# Solar_Phone_Charger.net
KiCad netlist of a schematic drawn in Altium Designer
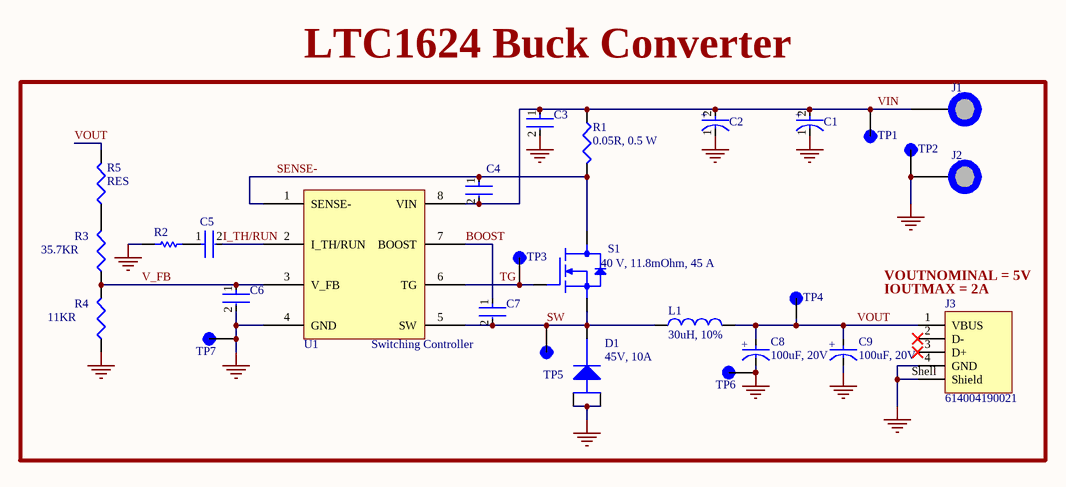
[diagram p0: Solar_Phone_Charger.SchDoc]

(export (version "E")
  (design (tool "Eeschema 10.0.6"))
  (components
    (comp (ref "C1")
      (value "T495X336M035ATE100")
      (footprint "FP-T495X336M035ATE100-MFG")
      (description "CAP TANT 33UF 20% 35V 2917")
      (fields (field (name "TOLERANCE") "20%"))
      (libsource (lib "") (part "203bc49f2ac43e59fd269a8c329ed05_1"))
    )
    (comp (ref "C2")
      (value "T495X336M035ATE100")
      (footprint "FP-T495X336M035ATE100-MFG")
      (description "CAP TANT 33UF 20% 35V 2917")
      (fields (field (name "TOLERANCE") "20%"))
      (libsource (lib "") (part "203bc49f2ac43e59fd269a8c329ed05_1"))
    )
    (comp (ref "C3")
      (value "C1206C104J5RACTU")
      (footprint "FP-C1206C-EB-MFG")
      (fields
        (field (name "MANUFACTURER") "KEMET")
        (field (name "OCTOPART") "https://octopart.com/c1206c104j5ractu-kemet-110335")
        (field (name "TOLERANCE") "0.05")
      )
      (libsource (lib "Altium Content Vault") (part "b4654b650e69147ec39a6b967a45e02"))
    )
    (comp (ref "C4")
      (value "C1206C102F1GACTU")
      (footprint "FP-C1206C-EB-MFG")
      (description "CAP CER 1000PF 100V 1% NP0 1206")
      (fields (field (name "TOLERANCE") "0.01") (field (name "MANUFACTURER") "KEMET"))
      (libsource (lib "Altium Content Vault") (part "b4654b650e69147ec39a6b967a45e02"))
    )
    (comp (ref "C5")
      (value "C0805C471J5GAC7210")
      (footprint "FP-C0805C-DN-MFG")
      (description "C0805 470 pF C0G 30ppm/°C 5.00% 50 V")
      (fields (field (name "TOLERANCE") "0.05") (field (name "MANUFACTURER") "KEMET"))
      (libsource (lib "Altium Content Vault") (part "b4654b650e69147ec39a6b967a45e02"))
    )
    (comp (ref "C6")
      (value "C0805C101K5GAC7210")
      (footprint "FP-C0805C-DN-MFG")
      (description "C0805 100 pF C0G 30ppm/°C 10.00% 50 V")
      (fields
        (field (name "OCTOPART") "https://octopart.com/c0805c101k5gac7210-kemet-11759675")
        (field (name "TOLERANCE") "0.1")
      )
      (libsource (lib "Altium Content Vault") (part "b4654b650e69147ec39a6b967a45e02"))
    )
    (comp (ref "C7")
      (value "C1206C104J5RACTU")
      (footprint "FP-C1206C-EB-MFG")
      (fields
        (field (name "MANUFACTURER") "KEMET")
        (field (name "OCTOPART") "https://octopart.com/c1206c104j5ractu-kemet-110335")
        (field (name "TOLERANCE") "0.05")
      )
      (libsource (lib "Altium Content Vault") (part "b4654b650e69147ec39a6b967a45e02"))
    )
    (comp (ref "C8")
      (value "100uF, 20V")
      (footprint "FP-TR3D-MFG")
      (fields (field (name "TOLERANCE") "10%"))
      (libsource (lib "Altium Content Vault") (part "203bc49f2ac43e59fd269a8c329ed05"))
    )
    (comp (ref "C9")
      (value "100uF, 20V")
      (footprint "FP-TR3D-MFG")
      (fields (field (name "TOLERANCE") "10%"))
      (libsource (lib "Altium Content Vault") (part "203bc49f2ac43e59fd269a8c329ed05"))
    )
    (comp (ref "D1")
      (value "45V, 10A")
      (footprint "PowerDI5")
      (description "Diode Schottky 45V 10A 5-Pin PowerDI T/R")
      (fields
        (field (name "MANUFACTURER") "Diodes")
        (field (name "MANUFACTURER PART NUMBER") "SDT10A45P5-13D")
      )
      (libsource (lib "Solar_Phone_Charger") (part "SDT10A45P5-13D"))
    )
    (comp (ref "J1")
      (value "4MM Banana Female Socket")
      (footprint "4MM Banana Female Socket")
      (libsource (lib "Solar_Phone_Charger") (part "4MM Banana Female Socket"))
    )
    (comp (ref "J2")
      (value "4MM Banana Female Socket")
      (footprint "4MM Banana Female Socket")
      (libsource (lib "Solar_Phone_Charger") (part "4MM Banana Female Socket"))
    )
    (comp (ref "J3")
      (value "614004190021")
      (footprint "614004190021")
      (libsource (lib "Altium Content Vault") (part "USB 2.0_Type A_Receptacle_1 Port"))
    )
    (comp (ref "L1")
      (value "30uH, 10%")
      (footprint "ERU24")
      (description "General Purpose Inductor, 30uH, 10%, 1 Element, Ferrite-Core, SMD, 9790")
      (fields (field (name "MANUFACTURER") "TDK") (field (name "MANUFACTURER PART NUMBER") "B82559A0303A024"))
      (libsource (lib "Solar_Phone_Charger") (part "B82559A0303A024"))
    )
    (comp (ref "R1")
      (value "0.05R, 0.5 W")
      (footprint "R1206")
      (description "Fixed Resistor, Metal Film, 0.5W, 0.05ohm, 0.5% +/-Tol, 100ppm/Cel, Surface Mount, 1206")
      (fields (field (name "MANUFACTURER") "Ohmite") (field (name "MANUFACTURER PART NUMBER") "KDV12DR050ET"))
      (libsource (lib "Solar_Phone_Charger") (part "KDV12DR050ET"))
    )
    (comp (ref "R2")
      (value "ERA8AEB682V")
      (footprint "RESC3216X70X50NL20T25")
      (fields (field (name "MANUFACTURER") "Panasonic"))
      (libsource (lib "Altium Content Vault") (part "RES"))
    )
    (comp (ref "R3")
      (value "35.7KR")
      (footprint "R1206")
      (description "1206 Thin Film Chip Resistor / 1206 SMD Resistor 0.05% 10PPM 35.7 Kohm")
      (fields
        (field (name "MANUFACTURER") "Panasonic")
        (field (name "MANUFACTURER PART NUMBER") "ERA-8ARW3572V")
      )
      (libsource (lib "Solar_Phone_Charger") (part "ERA-8ARW3572V"))
    )
    (comp (ref "R4")
      (value "11KR")
      (footprint "R1206")
      (description "Fixed Resistor, Thin Film, 0.25W, 11000ohm, 150V, 0.05% +/-Tol, 10ppm/Cel, Surface Mount, 1206")
      (fields
        (field (name "MANUFACTURER") "Panasonic")
        (field (name "MANUFACTURER PART NUMBER") "ERA-8ARW113V")
      )
      (libsource (lib "Solar_Phone_Charger") (part "ERA-8ARW113V"))
    )
    (comp (ref "R5")
      (value "RES")
      (footprint "R1206")
      (description "Generic 1206 Resistor")
      (fields
        (field (name "MANUFACTURER") "Panasonic")
        (field (name "MANUFACTURER PART NUMBER") "ERA-8ARW3572V")
      )
      (libsource (lib "Solar_Phone_Charger") (part "RES"))
    )
    (comp (ref "S1")
      (value "40 V, 11.8mOhm, 45 A")
      (footprint "DPAKSWITCH")
      (description "Single N-Channel Power MOSFET, 40V, 45A, 7.7mΩ DPAK 2500 tape and reel")
      (fields
        (field (name "MANUFACTURER") "ON Semiconductor")
        (field (name "MANUFACTURER PART NUMBER") "NVD5C478NLT4G")
      )
      (libsource (lib "Solar_Phone_Charger") (part "NVD5C478NLT4G"))
    )
    (comp (ref "TP1")
      (value "5287")
      (footprint "KEYSTONE_5287")
      (description "Blue Test Point")
      (libsource (lib "5287") (part "5287"))
    )
    (comp (ref "TP2")
      (value "5287")
      (footprint "KEYSTONE_5287")
      (description "Blue Test Point")
      (libsource (lib "5287") (part "5287"))
    )
    (comp (ref "TP3")
      (value "5287")
      (footprint "KEYSTONE_5287")
      (description "Blue Test Point")
      (libsource (lib "5287") (part "5287"))
    )
    (comp (ref "TP4")
      (value "5287")
      (footprint "KEYSTONE_5287")
      (description "Blue Test Point")
      (libsource (lib "5287") (part "5287"))
    )
    (comp (ref "TP5")
      (value "5287")
      (footprint "KEYSTONE_5287")
      (description "Blue Test Point")
      (libsource (lib "5287") (part "5287"))
    )
    (comp (ref "TP6")
      (value "5287")
      (footprint "KEYSTONE_5287")
      (description "Blue Test Point")
      (libsource (lib "5287") (part "5287"))
    )
    (comp (ref "TP7")
      (value "5287")
      (footprint "KEYSTONE_5287")
      (description "Blue Test Point")
      (libsource (lib "5287") (part "5287"))
    )
    (comp (ref "U1")
      (value "Switching Controller")
      (footprint "LTC1624")
      (description "Switching Controller, Current-mode, 2A, 225kHz Switching Freq-Max, CMOS, PDSO8")
      (fields
        (field (name "MANUFACTURER") "Analog Devices / Linear Technology")
        (field (name "MANUFACTURER PART NUMBER") "LTC1624IS8#TRPBF")
      )
      (libsource (lib "Solar_Phone_Charger") (part "LTC1624IS8#TRPBF"))
    )
  )
  (nets
    (net (code "1") (name "/BOOST") (class "Default")
      (node (ref "C7") (pin "1") (pinfunction "1_1") (pintype "passive"))
      (node (ref "U1") (pin "7") (pinfunction "BOOST_7") (pintype "passive"))
    )
    (net (code "2") (name "/I_TH{slash}RUN") (class "Default")
      (node (ref "C5") (pin "2") (pinfunction "2_2") (pintype "passive"))
      (node (ref "U1") (pin "2") (pinfunction "I_TH/RUN_2") (pintype "passive"))
    )
    (net (code "3") (name "/SENSE-") (class "Default")
      (node (ref "C4") (pin "1") (pinfunction "1_1") (pintype "passive"))
      (node (ref "R1") (pin "2") (pinfunction "2_2") (pintype "passive"))
      (node (ref "S1") (pin "2") (pinfunction "D_2") (pintype "passive"))
      (node (ref "U1") (pin "1") (pinfunction "SENSE-_1") (pintype "passive"))
    )
    (net (code "4") (name "/SW") (class "Default")
      (node (ref "C7") (pin "2") (pinfunction "2_2") (pintype "passive"))
      (node (ref "D1") (pin "3") (pinfunction "3_3") (pintype "passive"))
      (node (ref "L1") (pin "1") (pinfunction "1_1") (pintype "passive"))
      (node (ref "S1") (pin "3") (pinfunction "S_3") (pintype "passive"))
      (node (ref "TP5") (pin "1") (pinfunction "TP_1") (pintype "passive"))
      (node (ref "U1") (pin "5") (pinfunction "SW_5") (pintype "passive"))
    )
    (net (code "5") (name "/TG") (class "Default")
      (node (ref "S1") (pin "1") (pinfunction "G_1") (pintype "passive"))
      (node (ref "TP3") (pin "1") (pinfunction "TP_1") (pintype "passive"))
      (node (ref "U1") (pin "6") (pinfunction "TG_6") (pintype "passive"))
    )
    (net (code "6") (name "/VIN") (class "Default")
      (node (ref "C1") (pin "2") (pinfunction "A_2") (pintype "passive"))
      (node (ref "C2") (pin "2") (pinfunction "A_2") (pintype "passive"))
      (node (ref "C3") (pin "1") (pinfunction "1_1") (pintype "passive"))
      (node (ref "C4") (pin "2") (pinfunction "2_2") (pintype "passive"))
      (node (ref "J1") (pin "1") (pinfunction "1_1") (pintype "passive"))
      (node (ref "R1") (pin "1") (pinfunction "1_1") (pintype "passive"))
      (node (ref "TP1") (pin "1") (pinfunction "TP_1") (pintype "passive"))
      (node (ref "U1") (pin "8") (pinfunction "VIN_8") (pintype "passive"))
    )
    (net (code "7") (name "/VOUT") (class "Default")
      (node (ref "C8") (pin "2") (pinfunction "A_2") (pintype "passive"))
      (node (ref "C9") (pin "2") (pinfunction "A_2") (pintype "passive"))
      (node (ref "J3") (pin "1") (pinfunction "VBUS_1") (pintype "passive"))
      (node (ref "L1") (pin "2") (pinfunction "2_2") (pintype "passive"))
      (node (ref "R5") (pin "2") (pinfunction "2_2") (pintype "passive"))
      (node (ref "TP4") (pin "1") (pinfunction "TP_1") (pintype "passive"))
    )
    (net (code "8") (name "/V_FB") (class "Default")
      (node (ref "C6") (pin "1") (pinfunction "1_1") (pintype "passive"))
      (node (ref "R3") (pin "1") (pinfunction "1_1") (pintype "passive"))
      (node (ref "R4") (pin "2") (pinfunction "2_2") (pintype "passive"))
      (node (ref "U1") (pin "3") (pinfunction "V_FB_3") (pintype "passive"))
    )
    (net (code "9") (name "GND") (class "Default")
      (node (ref "C1") (pin "1") (pinfunction "C_1") (pintype "passive"))
      (node (ref "C2") (pin "1") (pinfunction "C_1") (pintype "passive"))
      (node (ref "C3") (pin "2") (pinfunction "2_2") (pintype "passive"))
      (node (ref "C6") (pin "2") (pinfunction "2_2") (pintype "passive"))
      (node (ref "C8") (pin "1") (pinfunction "C_1") (pintype "passive"))
      (node (ref "C9") (pin "1") (pinfunction "C_1") (pintype "passive"))
      (node (ref "D1") (pin "1") (pinfunction "1_1") (pintype "passive"))
      (node (ref "D1") (pin "2") (pinfunction "2_2") (pintype "passive"))
      (node (ref "J2") (pin "1") (pinfunction "1_1") (pintype "passive"))
      (node (ref "J3") (pin "4") (pinfunction "GND_4") (pintype "passive"))
      (node (ref "J3") (pin "Shell") (pinfunction "Shield_Shell") (pintype "passive"))
      (node (ref "R2") (pin "1") (pinfunction "1_1") (pintype "passive"))
      (node (ref "R4") (pin "1") (pinfunction "1_1") (pintype "passive"))
      (node (ref "TP2") (pin "1") (pinfunction "TP_1") (pintype "passive"))
      (node (ref "TP6") (pin "1") (pinfunction "TP_1") (pintype "passive"))
      (node (ref "TP7") (pin "1") (pinfunction "TP_1") (pintype "passive"))
      (node (ref "U1") (pin "4") (pinfunction "GND_4") (pintype "passive"))
    )
    (net (code "10") (name "Net-(C5-Pad1)") (class "Default")
      (node (ref "C5") (pin "1") (pinfunction "1_1") (pintype "passive"))
      (node (ref "R2") (pin "2") (pinfunction "2_2") (pintype "passive"))
    )
    (net (code "11") (name "Net-(R3-Pad2)") (class "Default")
      (node (ref "R3") (pin "2") (pinfunction "2_2") (pintype "passive"))
      (node (ref "R5") (pin "1") (pinfunction "1_1") (pintype "passive"))
    )
    (net (code "12") (name "unconnected-(J3-D+-Pad3)") (class "Default")
      (node (ref "J3") (pin "3") (pinfunction "D+_3") (pintype "passive+no_connect"))
    )
    (net (code "13") (name "unconnected-(J3-D--Pad2)") (class "Default")
      (node (ref "J3") (pin "2") (pinfunction "D-_2") (pintype "passive+no_connect"))
    )
  )
)
